# ESP32.net
KiCad netlist of a schematic drawn in Altium Designer
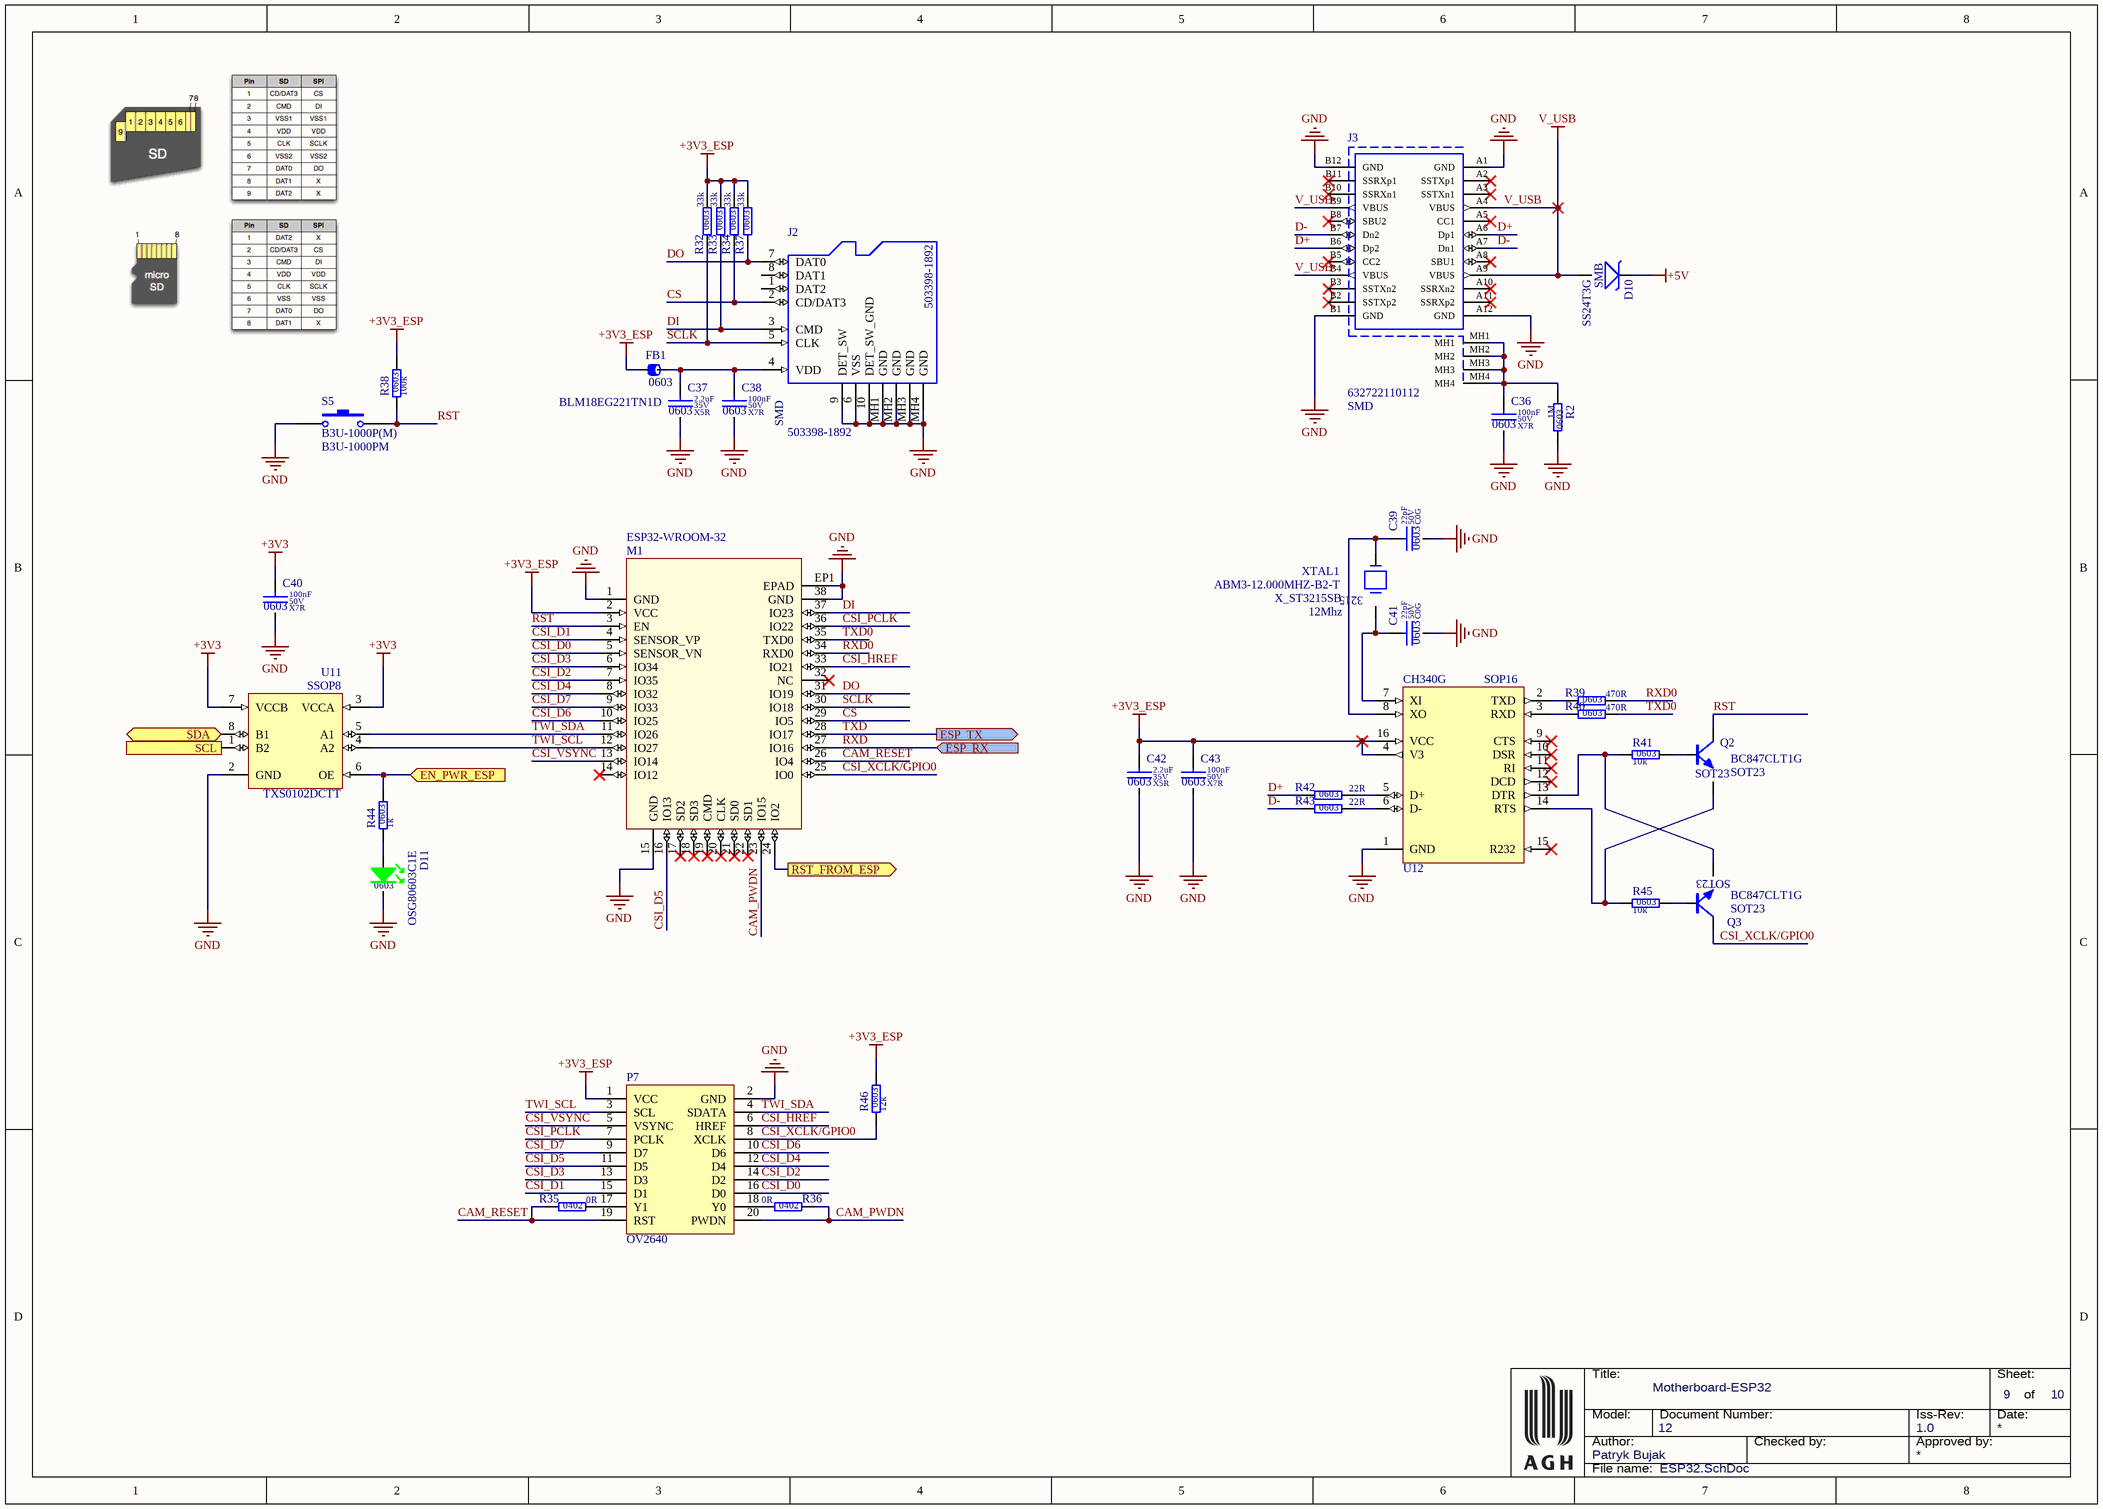
[diagram p0: ESP32.SchDoc]

(export (version "E")
  (design (tool "Eeschema 10.0.6"))
  (components
    (comp (ref "C36")
      (value "100nF")
      (footprint "C_0603_1608")
      (description "Capacitor")
      (fields
        (field (name "DIELECTRIC") "X7R")
        (field (name "VOLTAGE") "50V")
        (field (name "SCH_FOOTPRINT") "0603")
        (field (name "PART NUMBER") "C_100nF_50V_X7R_0603_5")
        (field (name "MANUFACTURER") "Samsung")
      )
      (libsource (lib "Library") (part "C"))
    )
    (comp (ref "C37")
      (value "2.2uF")
      (footprint "C_0603_1608")
      (description "Capacitor")
      (fields
        (field (name "DIELECTRIC") "X5R")
        (field (name "VOLTAGE") "35V")
        (field (name "SCH_FOOTPRINT") "0603")
        (field (name "PART NUMBER") "C_2.2uF_35V_X5R_0603_10")
        (field (name "MANUFACTURER") "Murata")
      )
      (libsource (lib "Library") (part "C"))
    )
    (comp (ref "C38")
      (value "100nF")
      (footprint "C_0603_1608")
      (description "Capacitor")
      (fields
        (field (name "DIELECTRIC") "X7R")
        (field (name "VOLTAGE") "50V")
        (field (name "SCH_FOOTPRINT") "0603")
        (field (name "PART NUMBER") "C_100nF_50V_X7R_0603_5")
        (field (name "MANUFACTURER") "Samsung")
      )
      (libsource (lib "Library") (part "C"))
    )
    (comp (ref "C39")
      (value "22pF")
      (footprint "C_0603_1608")
      (description "Capacitor")
      (fields
        (field (name "DIELECTRIC") "C0G")
        (field (name "VOLTAGE") "50V")
        (field (name "SCH_FOOTPRINT") "0603")
        (field (name "PART NUMBER") "C_22pF_50V_C0G_0603_5")
        (field (name "MANUFACTURER") "AVX")
      )
      (libsource (lib "Library") (part "C"))
    )
    (comp (ref "C40")
      (value "100nF")
      (footprint "C_0603_1608")
      (description "Capacitor")
      (fields
        (field (name "DIELECTRIC") "X7R")
        (field (name "VOLTAGE") "50V")
        (field (name "SCH_FOOTPRINT") "0603")
        (field (name "PART NUMBER") "C_100nF_50V_X7R_0603_5")
        (field (name "MANUFACTURER") "Samsung")
      )
      (libsource (lib "Library") (part "C"))
    )
    (comp (ref "C41")
      (value "22pF")
      (footprint "C_0603_1608")
      (description "Capacitor")
      (fields
        (field (name "DIELECTRIC") "C0G")
        (field (name "VOLTAGE") "50V")
        (field (name "SCH_FOOTPRINT") "0603")
        (field (name "PART NUMBER") "C_22pF_50V_C0G_0603_5")
        (field (name "MANUFACTURER") "AVX")
      )
      (libsource (lib "Library") (part "C"))
    )
    (comp (ref "C42")
      (value "2.2uF")
      (footprint "C_0603_1608")
      (description "Capacitor")
      (fields
        (field (name "DIELECTRIC") "X5R")
        (field (name "VOLTAGE") "35V")
        (field (name "SCH_FOOTPRINT") "0603")
        (field (name "PART NUMBER") "C_2.2uF_35V_X5R_0603_10")
        (field (name "MANUFACTURER") "Murata")
      )
      (libsource (lib "Library") (part "C"))
    )
    (comp (ref "C43")
      (value "100nF")
      (footprint "C_0603_1608")
      (description "Capacitor")
      (fields
        (field (name "DIELECTRIC") "X7R")
        (field (name "VOLTAGE") "50V")
        (field (name "SCH_FOOTPRINT") "0603")
        (field (name "PART NUMBER") "C_100nF_50V_X7R_0603_5")
        (field (name "MANUFACTURER") "Samsung")
      )
      (libsource (lib "Library") (part "C"))
    )
    (comp (ref "D10")
      (value "SS24T3G")
      (footprint "SMB_DO-214AA")
      (fields
        (field (name "SCH_FOOTPRINT") "SMB")
        (field (name "PART NUMBER") "DS_SS24_2A_40V_SMB")
        (field (name "VOLTAGE") "40V")
        (field (name "MANUFACTURER") "ON Semiconductor")
      )
      (libsource (lib "Library") (part "DS"))
    )
    (comp (ref "D11")
      (value "OSG80603C1E")
      (footprint "OL_0603_1608")
      (description "LED GREEN")
      (fields
        (field (name "SCH_FOOTPRINT") "0603")
        (field (name "PART NUMBER") "OL_G_0603_OSG80603C1E")
        (field (name "MANUFACTURER") "Optosupply")
      )
      (libsource (lib "Library") (part "OL_G"))
    )
    (comp (ref "FB1")
      (value "BLM18EG221TN1D")
      (footprint "FB_0603_1608")
      (description "Ferrite Bead")
      (fields
        (field (name "PART NUMBER") "FB_BLM18EG221TN1D")
        (field (name "SCH_FOOTPRINT") "0603")
        (field (name "MANUFACTURER") "Murata")
      )
      (libsource (lib "Library") (part "FB"))
    )
    (comp (ref "J2")
      (value "503398-1892")
      (footprint "503398-1892")
      (description "J_MICRO_SD")
      (fields
        (field (name "SCH_FOOTPRINT") "SMD")
        (field (name "MANUFACTURER PART NUMBER") "503398-1892")
        (field (name "PART NUMBER") "J_MICRO_SD_503398-1892")
        (field (name "MANUFACTURER") "Molex")
      )
      (libsource (lib "Library") (part "J_MICRO_SD_503398-1892"))
    )
    (comp (ref "J3")
      (value "632722110112")
      (footprint "J_USB_C_3.1_Vertical")
      (fields
        (field (name "PART NUMBER") "J_USB_C_3.1_Vertical")
        (field (name "SCH_FOOTPRINT") "SMD")
        (field (name "MANUFACTURER") "Wurth")
        (field (name "Comment") "USB C Connector")
      )
      (libsource (lib "Library") (part "J_USB_C_3.1"))
    )
    (comp (ref "M1")
      (value "ESP32-WROOM-32")
      (footprint "MOD_ESP_WROOM_32")
      (fields
        (field (name "PART NUMBER") "MOD_ESP32-WROOM-32")
        (field (name "MANUFACTURER") "ESPRESSIF")
        (field (name "Comment") "2.4 GHz Wi-Fi-and-Bluetooth combo chip")
      )
      (libsource (lib "Library") (part "MOD_ESP_WROOM_32"))
    )
    (comp (ref "P7")
      (value "OV2640")
      (footprint "H2X10_OV2640")
      (description "Header, 11-Pin, Dual row, Right Angle")
      (fields (field (name "PUBLISHER") "Altium Limited"))
      (libsource (lib "Patryk_ROZNE") (part "OV2640"))
    )
    (comp (ref "Q2")
      (value "BC847CLT1G")
      (footprint "SOT23_TO236_SC59")
      (fields
        (field (name "PART NUMBER") "QNP_BC847C_45V_0A1")
        (field (name "SCH_FOOTPRINT") "SOT23")
        (field (name "VOLTAGE") "45V")
        (field (name "MANUFACTURER") "ON Semiconductor")
      )
      (libsource (lib "Library") (part "QNP_BEC"))
    )
    (comp (ref "Q3")
      (value "BC847CLT1G")
      (footprint "SOT23_TO236_SC59")
      (fields
        (field (name "PART NUMBER") "QNP_BC847C_45V_0A1")
        (field (name "SCH_FOOTPRINT") "SOT23")
        (field (name "VOLTAGE") "45V")
        (field (name "MANUFACTURER") "ON Semiconductor")
      )
      (libsource (lib "Library") (part "QNP_BEC"))
    )
    (comp (ref "R2")
      (value "1M")
      (footprint "R_0603_1608")
      (fields
        (field (name "SCH_FOOTPRINT") "0603")
        (field (name "PART NUMBER") "R_1M_0603_1")
        (field (name "VOLTAGE") "50V")
        (field (name "POWER") "100mW")
      )
      (libsource (lib "Library") (part "R"))
    )
    (comp (ref "R32")
      (value "33k")
      (footprint "R_0603_1608")
      (fields
        (field (name "SCH_FOOTPRINT") "0603")
        (field (name "PART NUMBER") "R_33k_0603_1")
        (field (name "VOLTAGE") "75V")
        (field (name "POWER") "100mW")
      )
      (libsource (lib "Library") (part "R"))
    )
    (comp (ref "R33")
      (value "33k")
      (footprint "R_0603_1608")
      (fields
        (field (name "SCH_FOOTPRINT") "0603")
        (field (name "PART NUMBER") "R_33k_0603_1")
        (field (name "VOLTAGE") "75V")
        (field (name "POWER") "100mW")
      )
      (libsource (lib "Library") (part "R"))
    )
    (comp (ref "R34")
      (value "33k")
      (footprint "R_0603_1608")
      (fields
        (field (name "SCH_FOOTPRINT") "0603")
        (field (name "PART NUMBER") "R_33k_0603_1")
        (field (name "VOLTAGE") "75V")
        (field (name "POWER") "100mW")
      )
      (libsource (lib "Library") (part "R"))
    )
    (comp (ref "R35")
      (value "0R")
      (footprint "R_0402_1005")
      (fields
        (field (name "SCH_FOOTPRINT") "0402")
        (field (name "PART NUMBER") "R_0R_0402_5")
        (field (name "VOLTAGE") "50V")
        (field (name "POWER") "100mW")
      )
      (libsource (lib "Library") (part "R"))
    )
    (comp (ref "R36")
      (value "0R")
      (footprint "R_0402_1005")
      (fields
        (field (name "SCH_FOOTPRINT") "0402")
        (field (name "PART NUMBER") "R_0R_0402_5")
        (field (name "VOLTAGE") "50V")
        (field (name "POWER") "100mW")
      )
      (libsource (lib "Library") (part "R"))
    )
    (comp (ref "R37")
      (value "33k")
      (footprint "R_0603_1608")
      (fields
        (field (name "SCH_FOOTPRINT") "0603")
        (field (name "PART NUMBER") "R_33k_0603_1")
        (field (name "VOLTAGE") "75V")
        (field (name "POWER") "100mW")
      )
      (libsource (lib "Library") (part "R"))
    )
    (comp (ref "R38")
      (value "100k")
      (footprint "R_0603_1608")
      (fields
        (field (name "SCH_FOOTPRINT") "0603")
        (field (name "PART NUMBER") "R_100k_0603_1")
        (field (name "VOLTAGE") "50V")
        (field (name "POWER") "100mW")
      )
      (libsource (lib "Library") (part "R"))
    )
    (comp (ref "R39")
      (value "470R")
      (footprint "R_0603_1608")
      (fields
        (field (name "SCH_FOOTPRINT") "0603")
        (field (name "PART NUMBER") "R_470R_0603_1")
        (field (name "VOLTAGE") "50V")
        (field (name "POWER") "100mW")
      )
      (libsource (lib "Library") (part "R"))
    )
    (comp (ref "R40")
      (value "470R")
      (footprint "R_0603_1608")
      (fields
        (field (name "SCH_FOOTPRINT") "0603")
        (field (name "PART NUMBER") "R_470R_0603_1")
        (field (name "VOLTAGE") "50V")
        (field (name "POWER") "100mW")
      )
      (libsource (lib "Library") (part "R"))
    )
    (comp (ref "R41")
      (value "10k")
      (footprint "R_0603_1608")
      (fields
        (field (name "SCH_FOOTPRINT") "0603")
        (field (name "PART NUMBER") "R_10k_0603_1")
        (field (name "VOLTAGE") "75V")
        (field (name "POWER") "100mW")
      )
      (libsource (lib "Library") (part "R"))
    )
    (comp (ref "R42")
      (value "22R")
      (footprint "R_0603_1608")
      (fields
        (field (name "SCH_FOOTPRINT") "0603")
        (field (name "PART NUMBER") "R_22R_0603_5")
        (field (name "VOLTAGE") "50V")
        (field (name "POWER") "125mW")
      )
      (libsource (lib "Library") (part "R"))
    )
    (comp (ref "R43")
      (value "22R")
      (footprint "R_0603_1608")
      (fields
        (field (name "SCH_FOOTPRINT") "0603")
        (field (name "PART NUMBER") "R_22R_0603_5")
        (field (name "VOLTAGE") "50V")
        (field (name "POWER") "125mW")
      )
      (libsource (lib "Library") (part "R"))
    )
    (comp (ref "R44")
      (value "1k")
      (footprint "R_0603_1608")
      (fields
        (field (name "SCH_FOOTPRINT") "0603")
        (field (name "PART NUMBER") "R_1k_0603_1")
        (field (name "VOLTAGE") "75V")
        (field (name "POWER") "100mW")
      )
      (libsource (lib "Library") (part "R"))
    )
    (comp (ref "R45")
      (value "10k")
      (footprint "R_0603_1608")
      (fields
        (field (name "SCH_FOOTPRINT") "0603")
        (field (name "PART NUMBER") "R_10k_0603_1")
        (field (name "VOLTAGE") "75V")
        (field (name "POWER") "100mW")
      )
      (libsource (lib "Library") (part "R"))
    )
    (comp (ref "R46")
      (value "12k")
      (footprint "R_0603_1608")
      (fields
        (field (name "SCH_FOOTPRINT") "0603")
        (field (name "PART NUMBER") "R_12k_0603_1")
        (field (name "VOLTAGE") "50V")
        (field (name "POWER") "100mW")
      )
      (libsource (lib "Library") (part "R"))
    )
    (comp (ref "S5")
      (value "B3U-1000PM")
      (footprint "B3U-1000P")
      (description "Tact Switch")
      (fields
        (field (name "PART NUMBER") "S_B3U-1000PM")
        (field (name "SCH_FOOTPRINT") "B3U-1000P(M)")
        (field (name "MANUFACTURER") "OMRON")
      )
      (libsource (lib "Library") (part "S_TACTSWITCH"))
    )
    (comp (ref "U11")
      (value "TXS0102DCTT")
      (footprint "SSOP8_3x3")
      (fields
        (field (name "SCH_FOOTPRINT") "SSOP8")
        (field (name "PART NUMBER") "U_TXS0102DCTT")
        (field (name "MANUFACTURER") "Texas Instruments")
      )
      (libsource (lib "Library") (part "U_TXS0102_DCT_DCU"))
    )
    (comp (ref "U12")
      (value "CH340G")
      (footprint "SOP16_SO16_SOIC16_4X10X6")
      (fields
        (field (name "SCH_FOOTPRINT") "SOP16")
        (field (name "PART NUMBER") "U_CH340G")
        (field (name "MANUFACTURER") "WCH")
        (field (name "Comment") "USB to serial chip")
      )
      (libsource (lib "Library") (part "U_CH340_MSOP16"))
    )
    (comp (ref "XTAL1")
      (value "12Mhz")
      (footprint "X_ABM3-12.000MHZ-B2-T")
      (fields
        (field (name "PART NUMBER") "X_ABM3-12.000MHZ-B2-T")
        (field (name "MANUFACTURER PART NUMBER") "ABM3-12.000MHZ-B2-T")
        (field (name "SCH_FOOTPRINT") "X_ST3215SB")
        (field (name "MANUFACTURER") "ABM3")
        (field (name "Comment") "X_ST3215SB")
      )
      (libsource (lib "Library") (part "X_ST3215SB"))
    )
  )
  (nets
    (net (code "1") (name "+3V3") (class "Default")
      (node (ref "C40") (pin "1") (pinfunction "1_1") (pintype "passive"))
      (node (ref "U11") (pin "3") (pinfunction "VCCA_3") (pintype "input"))
      (node (ref "U11") (pin "7") (pinfunction "VCCB_7") (pintype "input"))
    )
    (net (code "2") (name "+3V3_ESP") (class "Default")
      (node (ref "C42") (pin "1") (pinfunction "1_1") (pintype "passive"))
      (node (ref "C43") (pin "1") (pinfunction "1_1") (pintype "passive"))
      (node (ref "FB1") (pin "1") (pintype "passive"))
      (node (ref "M1") (pin "2") (pinfunction "VCC_2") (pintype "input"))
      (node (ref "P7") (pin "1") (pinfunction "VCC_1") (pintype "passive"))
      (node (ref "R32") (pin "2") (pinfunction "2_2") (pintype "passive"))
      (node (ref "R33") (pin "2") (pinfunction "2_2") (pintype "passive"))
      (node (ref "R34") (pin "2") (pinfunction "2_2") (pintype "passive"))
      (node (ref "R37") (pin "2") (pinfunction "2_2") (pintype "passive"))
      (node (ref "R38") (pin "2") (pinfunction "2_2") (pintype "passive"))
      (node (ref "R46") (pin "2") (pinfunction "2_2") (pintype "passive"))
      (node (ref "U12") (pin "16") (pinfunction "VCC_16") (pintype "input"))
      (node (ref "U12") (pin "4") (pinfunction "V3_4") (pintype "output"))
    )
    (net (code "3") (name "+5V") (class "Default") (node (ref "D10") (pin "1") (pintype "passive")))
    (net (code "4") (name "/CAM_PWDN") (class "Default")
      (node (ref "M1") (pin "23") (pinfunction "IO15_23") (pintype "bidirectional"))
      (node (ref "P7") (pin "20") (pinfunction "PWDN_20") (pintype "passive"))
      (node (ref "R36") (pin "2") (pinfunction "2_2") (pintype "passive"))
    )
    (net (code "5") (name "/CAM_RESET") (class "Default")
      (node (ref "M1") (pin "26") (pinfunction "IO4_26") (pintype "bidirectional"))
      (node (ref "P7") (pin "19") (pinfunction "RST_19") (pintype "passive"))
      (node (ref "R35") (pin "1") (pinfunction "1_1") (pintype "passive"))
    )
    (net (code "6") (name "/CS") (class "Default")
      (node (ref "J2") (pin "2") (pinfunction "CD/DAT3_2") (pintype "bidirectional"))
      (node (ref "M1") (pin "29") (pinfunction "IO5_29") (pintype "bidirectional"))
      (node (ref "R34") (pin "1") (pinfunction "1_1") (pintype "passive"))
    )
    (net (code "7") (name "/CSI_D0") (class "Default")
      (node (ref "M1") (pin "5") (pinfunction "SENSOR_VN_5") (pintype "input"))
      (node (ref "P7") (pin "16") (pinfunction "D0_16") (pintype "passive"))
    )
    (net (code "8") (name "/CSI_D1") (class "Default")
      (node (ref "M1") (pin "4") (pinfunction "SENSOR_VP_4") (pintype "input"))
      (node (ref "P7") (pin "15") (pinfunction "D1_15") (pintype "passive"))
    )
    (net (code "9") (name "/CSI_D2") (class "Default")
      (node (ref "M1") (pin "7") (pinfunction "IO35_7") (pintype "input"))
      (node (ref "P7") (pin "14") (pinfunction "D2_14") (pintype "passive"))
    )
    (net (code "10") (name "/CSI_D3") (class "Default")
      (node (ref "M1") (pin "6") (pinfunction "IO34_6") (pintype "input"))
      (node (ref "P7") (pin "13") (pinfunction "D3_13") (pintype "passive"))
    )
    (net (code "11") (name "/CSI_D4") (class "Default")
      (node (ref "M1") (pin "8") (pinfunction "IO32_8") (pintype "bidirectional"))
      (node (ref "P7") (pin "12") (pinfunction "D4_12") (pintype "passive"))
    )
    (net (code "12") (name "/CSI_D5") (class "Default")
      (node (ref "M1") (pin "16") (pinfunction "IO13_16") (pintype "bidirectional"))
      (node (ref "P7") (pin "11") (pinfunction "D5_11") (pintype "passive"))
    )
    (net (code "13") (name "/CSI_D6") (class "Default")
      (node (ref "M1") (pin "10") (pinfunction "IO25_10") (pintype "bidirectional"))
      (node (ref "P7") (pin "10") (pinfunction "D6_10") (pintype "passive"))
    )
    (net (code "14") (name "/CSI_D7") (class "Default")
      (node (ref "M1") (pin "9") (pinfunction "IO33_9") (pintype "bidirectional"))
      (node (ref "P7") (pin "9") (pinfunction "D7_9") (pintype "passive"))
    )
    (net (code "15") (name "/CSI_HREF") (class "Default")
      (node (ref "M1") (pin "33") (pinfunction "IO21_33") (pintype "bidirectional"))
      (node (ref "P7") (pin "6") (pinfunction "HREF_6") (pintype "passive"))
    )
    (net (code "16") (name "/CSI_PCLK") (class "Default")
      (node (ref "M1") (pin "36") (pinfunction "IO22_36") (pintype "bidirectional"))
      (node (ref "P7") (pin "7") (pinfunction "PCLK_7") (pintype "passive"))
    )
    (net (code "17") (name "/CSI_VSYNC") (class "Default")
      (node (ref "M1") (pin "13") (pinfunction "IO14_13") (pintype "bidirectional"))
      (node (ref "P7") (pin "5") (pinfunction "VSYNC_5") (pintype "passive"))
    )
    (net (code "18") (name "/CSI_XCLK{slash}GPIO0") (class "Default")
      (node (ref "M1") (pin "25") (pinfunction "IO0_25") (pintype "bidirectional"))
      (node (ref "P7") (pin "8") (pinfunction "XCLK_8") (pintype "passive"))
      (node (ref "Q3") (pin "3") (pinfunction "C_3") (pintype "passive"))
      (node (ref "R46") (pin "1") (pinfunction "1_1") (pintype "passive"))
    )
    (net (code "19") (name "/D+") (class "Default")
      (node (ref "J3") (pin "A6") (pinfunction "Dp1_A6") (pintype "bidirectional"))
      (node (ref "J3") (pin "B6") (pinfunction "Dp2_B6") (pintype "bidirectional"))
      (node (ref "R42") (pin "1") (pinfunction "1_1") (pintype "passive"))
    )
    (net (code "20") (name "/D-") (class "Default")
      (node (ref "J3") (pin "A7") (pinfunction "Dn1_A7") (pintype "bidirectional"))
      (node (ref "J3") (pin "B7") (pinfunction "Dn2_B7") (pintype "bidirectional"))
      (node (ref "R43") (pin "1") (pinfunction "1_1") (pintype "passive"))
    )
    (net (code "21") (name "/DI") (class "Default")
      (node (ref "J2") (pin "3") (pinfunction "CMD_3") (pintype "input"))
      (node (ref "M1") (pin "37") (pinfunction "IO23_37") (pintype "bidirectional"))
      (node (ref "R33") (pin "1") (pinfunction "1_1") (pintype "passive"))
    )
    (net (code "22") (name "/DO") (class "Default")
      (node (ref "J2") (pin "7") (pinfunction "DAT0_7") (pintype "bidirectional"))
      (node (ref "M1") (pin "31") (pinfunction "IO19_31") (pintype "bidirectional"))
      (node (ref "R37") (pin "1") (pinfunction "1_1") (pintype "passive"))
    )
    (net (code "23") (name "/EN_PWR_ESP") (class "Default")
      (node (ref "R44") (pin "2") (pinfunction "2_2") (pintype "passive"))
      (node (ref "U11") (pin "6") (pinfunction "OE_6") (pintype "input"))
    )
    (net (code "24") (name "/RST") (class "Default")
      (node (ref "M1") (pin "3") (pinfunction "EN_3") (pintype "input"))
      (node (ref "Q2") (pin "3") (pinfunction "C_3") (pintype "passive"))
      (node (ref "R38") (pin "1") (pinfunction "1_1") (pintype "passive"))
      (node (ref "S5") (pin "2") (pinfunction "2_2") (pintype "passive"))
    )
    (net (code "25") (name "/RST_FROM_ESP") (class "Default")
      (node (ref "M1") (pin "24") (pinfunction "IO2_24") (pintype "bidirectional"))
    )
    (net (code "26") (name "/RXD") (class "Default")
      (node (ref "M1") (pin "27") (pinfunction "IO16_27") (pintype "bidirectional"))
    )
    (net (code "27") (name "/RXD0") (class "Default")
      (node (ref "M1") (pin "34") (pinfunction "RXD0_34") (pintype "bidirectional"))
      (node (ref "R39") (pin "2") (pinfunction "2_2") (pintype "passive"))
    )
    (net (code "28") (name "/SCL") (class "Default")
      (node (ref "U11") (pin "1") (pinfunction "B2_1") (pintype "bidirectional"))
    )
    (net (code "29") (name "/SCLK") (class "Default")
      (node (ref "J2") (pin "5") (pinfunction "CLK_5") (pintype "input"))
      (node (ref "M1") (pin "30") (pinfunction "IO18_30") (pintype "bidirectional"))
      (node (ref "R32") (pin "1") (pinfunction "1_1") (pintype "passive"))
    )
    (net (code "30") (name "/SDA") (class "Default")
      (node (ref "U11") (pin "8") (pinfunction "B1_8") (pintype "bidirectional"))
    )
    (net (code "31") (name "/TWI_SCL") (class "Default")
      (node (ref "M1") (pin "12") (pinfunction "IO27_12") (pintype "bidirectional"))
      (node (ref "P7") (pin "3") (pinfunction "SCL_3") (pintype "passive"))
      (node (ref "U11") (pin "4") (pinfunction "A2_4") (pintype "bidirectional"))
    )
    (net (code "32") (name "/TWI_SDA") (class "Default")
      (node (ref "M1") (pin "11") (pinfunction "IO26_11") (pintype "bidirectional"))
      (node (ref "P7") (pin "4") (pinfunction "SDATA_4") (pintype "passive"))
      (node (ref "U11") (pin "5") (pinfunction "A1_5") (pintype "bidirectional"))
    )
    (net (code "33") (name "/TXD") (class "Default")
      (node (ref "M1") (pin "28") (pinfunction "IO17_28") (pintype "bidirectional"))
    )
    (net (code "34") (name "/TXD0") (class "Default")
      (node (ref "M1") (pin "35") (pinfunction "TXD0_35") (pintype "bidirectional"))
      (node (ref "R40") (pin "2") (pinfunction "2_2") (pintype "passive"))
    )
    (net (code "35") (name "GND") (class "Default")
      (node (ref "C36") (pin "2") (pinfunction "2_2") (pintype "passive"))
      (node (ref "C37") (pin "2") (pinfunction "2_2") (pintype "passive"))
      (node (ref "C38") (pin "2") (pinfunction "2_2") (pintype "passive"))
      (node (ref "C39") (pin "2") (pinfunction "2_2") (pintype "passive"))
      (node (ref "C40") (pin "2") (pinfunction "2_2") (pintype "passive"))
      (node (ref "C41") (pin "2") (pinfunction "2_2") (pintype "passive"))
      (node (ref "C42") (pin "2") (pinfunction "2_2") (pintype "passive"))
      (node (ref "C43") (pin "2") (pinfunction "2_2") (pintype "passive"))
      (node (ref "D11") (pin "1") (pinfunction "K_1") (pintype "passive"))
      (node (ref "J2") (pin "10") (pinfunction "DET_SW_GND_10") (pintype "power_in"))
      (node (ref "J2") (pin "6") (pinfunction "VSS_6") (pintype "power_in"))
      (node (ref "J2") (pin "9") (pinfunction "DET_SW_9") (pintype "passive"))
      (node (ref "J2") (pin "MH1") (pinfunction "GND_MH1") (pintype "power_in"))
      (node (ref "J2") (pin "MH2") (pinfunction "GND_MH2") (pintype "power_in"))
      (node (ref "J2") (pin "MH3") (pinfunction "GND_MH3") (pintype "power_in"))
      (node (ref "J2") (pin "MH4") (pinfunction "GND_MH4") (pintype "power_in"))
      (node (ref "J3") (pin "A1") (pinfunction "GND_A1") (pintype "power_in"))
      (node (ref "J3") (pin "A12") (pinfunction "GND_A12") (pintype "power_in"))
      (node (ref "J3") (pin "B1") (pinfunction "GND_B1") (pintype "power_in"))
      (node (ref "J3") (pin "B12") (pinfunction "GND_B12") (pintype "power_in"))
      (node (ref "M1") (pin "1") (pinfunction "GND_1") (pintype "power_in"))
      (node (ref "M1") (pin "15") (pinfunction "GND_15") (pintype "power_in"))
      (node (ref "M1") (pin "38") (pinfunction "GND_38") (pintype "power_in"))
      (node (ref "M1") (pin "EP1") (pinfunction "EPAD_EP1") (pintype "power_in"))
      (node (ref "P7") (pin "2") (pinfunction "GND_2") (pintype "passive"))
      (node (ref "R2") (pin "2") (pinfunction "2_2") (pintype "passive"))
      (node (ref "S5") (pin "1") (pinfunction "1_1") (pintype "passive"))
      (node (ref "U11") (pin "2") (pinfunction "GND_2") (pintype "power_in"))
      (node (ref "U12") (pin "1") (pinfunction "GND_1") (pintype "power_in"))
    )
    (net (code "36") (name "Net-(C36-Pad1)") (class "Default")
      (node (ref "C36") (pin "1") (pinfunction "1_1") (pintype "passive"))
      (node (ref "J3") (pin "MH1") (pinfunction "MH1_MH1") (pintype "passive"))
      (node (ref "J3") (pin "MH2") (pinfunction "MH2_MH2") (pintype "passive"))
      (node (ref "J3") (pin "MH3") (pinfunction "MH3_MH3") (pintype "passive"))
      (node (ref "J3") (pin "MH4") (pinfunction "MH4_MH4") (pintype "passive"))
      (node (ref "R2") (pin "1") (pinfunction "1_1") (pintype "passive"))
    )
    (net (code "37") (name "Net-(D11-A)") (class "Default")
      (node (ref "D11") (pin "2") (pinfunction "A_2") (pintype "passive"))
      (node (ref "R44") (pin "1") (pinfunction "1_1") (pintype "passive"))
    )
    (net (code "38") (name "Net-(J2-VDD)") (class "Default")
      (node (ref "C37") (pin "1") (pinfunction "1_1") (pintype "passive"))
      (node (ref "C38") (pin "1") (pinfunction "1_1") (pintype "passive"))
      (node (ref "FB1") (pin "2") (pintype "passive"))
      (node (ref "J2") (pin "4") (pinfunction "VDD_4") (pintype "input"))
    )
    (net (code "39") (name "Net-(P7-Y0)") (class "Default")
      (node (ref "P7") (pin "18") (pinfunction "Y0_18") (pintype "passive"))
      (node (ref "R36") (pin "1") (pinfunction "1_1") (pintype "passive"))
    )
    (net (code "40") (name "Net-(P7-Y1)") (class "Default")
      (node (ref "P7") (pin "17") (pinfunction "Y1_17") (pintype "passive"))
      (node (ref "R35") (pin "2") (pinfunction "2_2") (pintype "passive"))
    )
    (net (code "41") (name "Net-(Q2-B)") (class "Default")
      (node (ref "Q2") (pin "1") (pinfunction "B_1") (pintype "passive"))
      (node (ref "R41") (pin "2") (pinfunction "2_2") (pintype "passive"))
    )
    (net (code "42") (name "Net-(Q2-E)") (class "Default")
      (node (ref "Q2") (pin "2") (pinfunction "E_2") (pintype "passive"))
      (node (ref "R45") (pin "1") (pinfunction "1_1") (pintype "passive"))
      (node (ref "U12") (pin "14") (pinfunction "RTS_14") (pintype "output"))
    )
    (net (code "43") (name "Net-(Q3-B)") (class "Default")
      (node (ref "Q3") (pin "1") (pinfunction "B_1") (pintype "passive"))
      (node (ref "R45") (pin "2") (pinfunction "2_2") (pintype "passive"))
    )
    (net (code "44") (name "Net-(Q3-E)") (class "Default")
      (node (ref "Q3") (pin "2") (pinfunction "E_2") (pintype "passive"))
      (node (ref "R41") (pin "1") (pinfunction "1_1") (pintype "passive"))
      (node (ref "U12") (pin "13") (pinfunction "DTR_13") (pintype "output"))
    )
    (net (code "45") (name "Net-(U12-D+)") (class "Default")
      (node (ref "R42") (pin "2") (pinfunction "2_2") (pintype "passive"))
      (node (ref "U12") (pin "5") (pinfunction "D+_5") (pintype "bidirectional"))
    )
    (net (code "46") (name "Net-(U12-D-)") (class "Default")
      (node (ref "R43") (pin "2") (pinfunction "2_2") (pintype "passive"))
      (node (ref "U12") (pin "6") (pinfunction "D-_6") (pintype "bidirectional"))
    )
    (net (code "47") (name "Net-(U12-RXD)") (class "Default")
      (node (ref "R40") (pin "1") (pinfunction "1_1") (pintype "passive"))
      (node (ref "U12") (pin "3") (pinfunction "RXD_3") (pintype "input"))
    )
    (net (code "48") (name "Net-(U12-TXD)") (class "Default")
      (node (ref "R39") (pin "1") (pinfunction "1_1") (pintype "passive"))
      (node (ref "U12") (pin "2") (pinfunction "TXD_2") (pintype "output"))
    )
    (net (code "49") (name "Net-(U12-XI)") (class "Default")
      (node (ref "C41") (pin "1") (pinfunction "1_1") (pintype "passive"))
      (node (ref "U12") (pin "7") (pinfunction "XI_7") (pintype "input"))
      (node (ref "XTAL1") (pin "1") (pinfunction "1_1") (pintype "passive"))
    )
    (net (code "50") (name "Net-(U12-XO)") (class "Default")
      (node (ref "C39") (pin "1") (pinfunction "1_1") (pintype "passive"))
      (node (ref "U12") (pin "8") (pinfunction "XO_8") (pintype "input"))
      (node (ref "XTAL1") (pin "2") (pinfunction "2_2") (pintype "passive"))
    )
    (net (code "51") (name "V_USB") (class "Default")
      (node (ref "D10") (pin "2") (pintype "passive"))
      (node (ref "J3") (pin "A4") (pinfunction "VBUS_A4") (pintype "output"))
      (node (ref "J3") (pin "A9") (pinfunction "VBUS_A9") (pintype "output"))
      (node (ref "J3") (pin "B4") (pinfunction "VBUS_B4") (pintype "output"))
      (node (ref "J3") (pin "B9") (pinfunction "VBUS_B9") (pintype "output"))
    )
    (net (code "52") (name "unconnected-(J2-DAT1-Pad8)") (class "Default")
      (node (ref "J2") (pin "8") (pinfunction "DAT1_8") (pintype "bidirectional"))
    )
    (net (code "53") (name "unconnected-(J2-DAT2-Pad1)") (class "Default")
      (node (ref "J2") (pin "1") (pinfunction "DAT2_1") (pintype "bidirectional"))
    )
    (net (code "54") (name "unconnected-(J3-CC1-PadA5)") (class "Default")
      (node (ref "J3") (pin "A5") (pinfunction "CC1_A5") (pintype "passive+no_connect"))
    )
    (net (code "55") (name "unconnected-(J3-CC2-PadB5)") (class "Default")
      (node (ref "J3") (pin "B5") (pinfunction "CC2_B5") (pintype "bidirectional+no_connect"))
    )
    (net (code "56") (name "unconnected-(J3-SBU1-PadA8)") (class "Default")
      (node (ref "J3") (pin "A8") (pinfunction "SBU1_A8") (pintype "bidirectional+no_connect"))
    )
    (net (code "57") (name "unconnected-(J3-SBU2-PadB8)") (class "Default")
      (node (ref "J3") (pin "B8") (pinfunction "SBU2_B8") (pintype "bidirectional+no_connect"))
    )
    (net (code "58") (name "unconnected-(J3-SSRXn1-PadB10)") (class "Default")
      (node (ref "J3") (pin "B10") (pinfunction "SSRXn1_B10") (pintype "passive+no_connect"))
    )
    (net (code "59") (name "unconnected-(J3-SSRXn2-PadA10)") (class "Default")
      (node (ref "J3") (pin "A10") (pinfunction "SSRXn2_A10") (pintype "passive+no_connect"))
    )
    (net (code "60") (name "unconnected-(J3-SSRXp1-PadB11)") (class "Default")
      (node (ref "J3") (pin "B11") (pinfunction "SSRXp1_B11") (pintype "passive+no_connect"))
    )
    (net (code "61") (name "unconnected-(J3-SSRXp2-PadA11)") (class "Default")
      (node (ref "J3") (pin "A11") (pinfunction "SSRXp2_A11") (pintype "passive+no_connect"))
    )
    (net (code "62") (name "unconnected-(J3-SSTXn1-PadA3)") (class "Default")
      (node (ref "J3") (pin "A3") (pinfunction "SSTXn1_A3") (pintype "passive+no_connect"))
    )
    (net (code "63") (name "unconnected-(J3-SSTXn2-PadB3)") (class "Default")
      (node (ref "J3") (pin "B3") (pinfunction "SSTXn2_B3") (pintype "passive+no_connect"))
    )
    (net (code "64") (name "unconnected-(J3-SSTXp1-PadA2)") (class "Default")
      (node (ref "J3") (pin "A2") (pinfunction "SSTXp1_A2") (pintype "passive+no_connect"))
    )
    (net (code "65") (name "unconnected-(J3-SSTXp2-PadB2)") (class "Default")
      (node (ref "J3") (pin "B2") (pinfunction "SSTXp2_B2") (pintype "passive+no_connect"))
    )
    (net (code "66") (name "unconnected-(M1-CLK-Pad20)") (class "Default")
      (node (ref "M1") (pin "20") (pinfunction "CLK_20") (pintype "bidirectional+no_connect"))
    )
    (net (code "67") (name "unconnected-(M1-CMD-Pad19)") (class "Default")
      (node (ref "M1") (pin "19") (pinfunction "CMD_19") (pintype "bidirectional+no_connect"))
    )
    (net (code "68") (name "unconnected-(M1-IO12-Pad14)") (class "Default")
      (node (ref "M1") (pin "14") (pinfunction "IO12_14") (pintype "bidirectional+no_connect"))
    )
    (net (code "69") (name "unconnected-(M1-NC-Pad32)") (class "Default")
      (node (ref "M1") (pin "32") (pinfunction "NC_32") (pintype "passive+no_connect"))
    )
    (net (code "70") (name "unconnected-(M1-SD0-Pad21)") (class "Default")
      (node (ref "M1") (pin "21") (pinfunction "SD0_21") (pintype "bidirectional+no_connect"))
    )
    (net (code "71") (name "unconnected-(M1-SD1-Pad22)") (class "Default")
      (node (ref "M1") (pin "22") (pinfunction "SD1_22") (pintype "bidirectional+no_connect"))
    )
    (net (code "72") (name "unconnected-(M1-SD2-Pad17)") (class "Default")
      (node (ref "M1") (pin "17") (pinfunction "SD2_17") (pintype "bidirectional+no_connect"))
    )
    (net (code "73") (name "unconnected-(M1-SD3-Pad18)") (class "Default")
      (node (ref "M1") (pin "18") (pinfunction "SD3_18") (pintype "bidirectional+no_connect"))
    )
    (net (code "74") (name "unconnected-(U12-CTS-Pad9)") (class "Default")
      (node (ref "U12") (pin "9") (pinfunction "CTS_9") (pintype "input+no_connect"))
    )
    (net (code "75") (name "unconnected-(U12-DCD-Pad12)") (class "Default")
      (node (ref "U12") (pin "12") (pinfunction "DCD_12") (pintype "output+no_connect"))
    )
    (net (code "76") (name "unconnected-(U12-DSR-Pad10)") (class "Default")
      (node (ref "U12") (pin "10") (pinfunction "DSR_10") (pintype "input+no_connect"))
    )
    (net (code "77") (name "unconnected-(U12-R232-Pad15)") (class "Default")
      (node (ref "U12") (pin "15") (pinfunction "R232_15") (pintype "input+no_connect"))
    )
    (net (code "78") (name "unconnected-(U12-RI-Pad11)") (class "Default")
      (node (ref "U12") (pin "11") (pinfunction "RI_11") (pintype "input+no_connect"))
    )
  )
)
